# POWER.net
KiCad netlist of a schematic drawn in Altium Designer
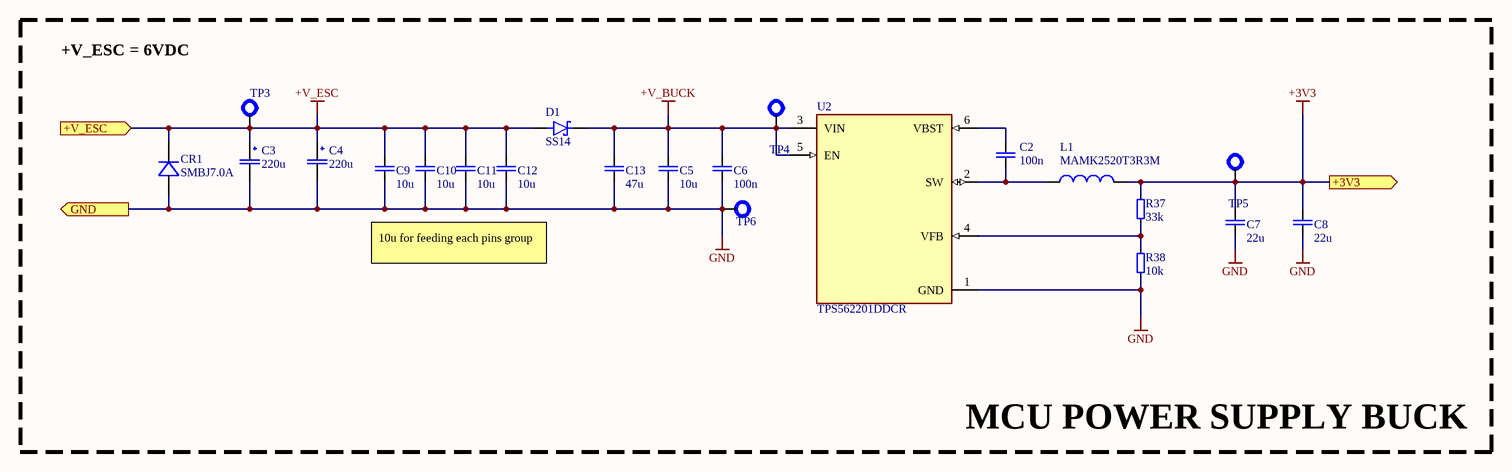
[diagram p0: POWER.SchDoc]

(export (version "E")
  (design (tool "Eeschema 10.0.6"))
  (components
    (comp (ref "C2")
      (value "100n")
      (footprint "C0402")
      (description "Generic SMD 0402 Ceramic Capacitor")
      (libsource (lib "PolSl Racing - Electrical") (part "Capacitor"))
    )
    (comp (ref "C3")
      (value "220u")
      (footprint "CAP_PC_8X10_NCH")
      (description "No Description Available")
      (fields
        (field (name "MANUFACTURER_PART_NUMBER") "PCJ1C221MCL4GS")
        (field (name "COPYRIGHT") "Copyright (C) 2026 Ultra Librarian. All rights reserved.")
      )
      (libsource (lib "Tractor2000") (part "PCJ1C221MCL4GS"))
    )
    (comp (ref "C4")
      (value "220u")
      (footprint "CAP_PC_8X10_NCH")
      (description "No Description Available")
      (fields
        (field (name "MANUFACTURER_PART_NUMBER") "PCJ1C221MCL4GS")
        (field (name "COPYRIGHT") "Copyright (C) 2026 Ultra Librarian. All rights reserved.")
      )
      (libsource (lib "Tractor2000") (part "PCJ1C221MCL4GS"))
    )
    (comp (ref "C5")
      (value "10u")
      (footprint "C0603")
      (description "Generic 0603 SMD Ceramic Capacitor")
      (libsource (lib "PolSl Racing - Electrical") (part "Capacitor"))
    )
    (comp (ref "C6")
      (value "100n")
      (footprint "C0603")
      (description "Generic 0603 SMD Ceramic Capacitor")
      (libsource (lib "PolSl Racing - Electrical") (part "Capacitor"))
    )
    (comp (ref "C7")
      (value "22u")
      (footprint "C0603")
      (description "Generic 0603 SMD Ceramic Capacitor")
      (libsource (lib "PolSl Racing - Electrical") (part "Capacitor"))
    )
    (comp (ref "C8")
      (value "22u")
      (footprint "C0603")
      (description "Generic 0603 SMD Ceramic Capacitor")
      (libsource (lib "PolSl Racing - Electrical") (part "Capacitor"))
    )
    (comp (ref "C9")
      (value "10u")
      (footprint "C0805")
      (description "Generic 0805 SMD Ceramic Capacitor")
      (libsource (lib "PolSl Racing - Electrical") (part "Capacitor"))
    )
    (comp (ref "C10")
      (value "10u")
      (footprint "C0805")
      (description "Generic 0805 SMD Ceramic Capacitor")
      (libsource (lib "PolSl Racing - Electrical") (part "Capacitor"))
    )
    (comp (ref "C11")
      (value "10u")
      (footprint "C0805")
      (description "Generic 0805 SMD Ceramic Capacitor")
      (libsource (lib "PolSl Racing - Electrical") (part "Capacitor"))
    )
    (comp (ref "C12")
      (value "10u")
      (footprint "C0805")
      (description "Generic 0805 SMD Ceramic Capacitor")
      (libsource (lib "PolSl Racing - Electrical") (part "Capacitor"))
    )
    (comp (ref "C13")
      (value "47u")
      (footprint "C1210")
      (description "Generic 1210 SMD Ceramic Capacitor")
      (libsource (lib "PolSl Racing - Electrical") (part "Capacitor"))
    )
    (comp (ref "CR1")
      (value "SMBJ7.0A")
      (footprint "SMBJSeries_LTF")
      (description "Description")
      (fields (field (name "COPYRIGHT") "Copyright (C) 2025 Ultra Librarian. All rights reserved."))
      (libsource (lib "Tractor2000") (part "SMBJ7.0A"))
    )
    (comp (ref "D1")
      (value "SS14")
      (footprint "DIOM4325X250N")
      (description "1A, 40V, Schottky Rectifier")
      (fields (field (name "MF") "Taiwan Semiconductor"))
      (libsource (lib "Tractor2000") (part "SS14"))
    )
    (comp (ref "L1")
      (value "MAMK2520T3R3M")
      (footprint "INDC2520X120N")
      (description "3.3 ÂµH Shielded Drum Core, Wirewound Inductor 1.7 A 156mOhm Max 1008 (2520 Metric)")
      (fields (field (name "MF") "Taiyo Yuden"))
      (libsource (lib "Tractor2000") (part "MAMK2520T3R3M"))
    )
    (comp (ref "R37")
      (value "33k")
      (footprint "R0402")
      (description "Generic 0402 SMD Resistor")
      (libsource (lib "PolSl Racing - Electrical") (part "Resistor"))
    )
    (comp (ref "R38")
      (value "10k")
      (footprint "R0402")
      (description "Generic 0402 SMD Resistor")
      (libsource (lib "PolSl Racing - Electrical") (part "Resistor"))
    )
    (comp (ref "TP3") (value "TP") (footprint "TP") (libsource (lib "Tractor2000") (part "TP")))
    (comp (ref "TP4") (value "TP") (footprint "TP") (libsource (lib "Tractor2000") (part "TP")))
    (comp (ref "TP5") (value "TP") (footprint "TP") (libsource (lib "Tractor2000") (part "TP")))
    (comp (ref "TP6") (value "TP") (footprint "TP") (libsource (lib "Tractor2000") (part "TP")))
    (comp (ref "U2")
      (value "TPS562201DDCR")
      (footprint "SOT95P280X110-6N")
      (description "4.5 V to 17 V input, 2 A output, synchronous step-down converter in Eco-mode")
      (fields (field (name "MF") "Texas Instruments"))
      (libsource (lib "Tractor2000") (part "TPS562201DDCR"))
    )
  )
  (nets
    (net (code "1") (name "+3V3") (class "Default")
      (node (ref "C7") (pin "2") (pinfunction "2_2") (pintype "passive"))
      (node (ref "C8") (pin "2") (pinfunction "2_2") (pintype "passive"))
      (node (ref "L1") (pin "2") (pinfunction "2_2") (pintype "passive"))
      (node (ref "R37") (pin "2") (pinfunction "2_2") (pintype "passive"))
    )
    (net (code "2") (name "+V_BUCK") (class "Default")
      (node (ref "C13") (pin "2") (pinfunction "2_2") (pintype "passive"))
      (node (ref "C5") (pin "2") (pinfunction "2_2") (pintype "passive"))
      (node (ref "C6") (pin "2") (pinfunction "2_2") (pintype "passive"))
      (node (ref "D1") (pin "C") (pinfunction "K_C") (pintype "passive"))
      (node (ref "U2") (pin "3") (pinfunction "VIN_3") (pintype "power_in"))
      (node (ref "U2") (pin "5") (pinfunction "EN_5") (pintype "input"))
    )
    (net (code "3") (name "+V_ESC") (class "Default")
      (node (ref "C10") (pin "2") (pinfunction "2_2") (pintype "passive"))
      (node (ref "C11") (pin "2") (pinfunction "2_2") (pintype "passive"))
      (node (ref "C12") (pin "2") (pinfunction "2_2") (pintype "passive"))
      (node (ref "C3") (pin "1") (pinfunction "1_1") (pintype "passive"))
      (node (ref "C4") (pin "1") (pinfunction "1_1") (pintype "passive"))
      (node (ref "C9") (pin "2") (pinfunction "2_2") (pintype "passive"))
      (node (ref "CR1") (pin "1") (pinfunction "1_1") (pintype "passive"))
      (node (ref "D1") (pin "A") (pinfunction "A_A") (pintype "passive"))
    )
    (net (code "4") (name "GND") (class "Default")
      (node (ref "C10") (pin "1") (pinfunction "1_1") (pintype "passive"))
      (node (ref "C11") (pin "1") (pinfunction "1_1") (pintype "passive"))
      (node (ref "C12") (pin "1") (pinfunction "1_1") (pintype "passive"))
      (node (ref "C13") (pin "1") (pinfunction "1_1") (pintype "passive"))
      (node (ref "C3") (pin "2") (pinfunction "2_2") (pintype "passive"))
      (node (ref "C4") (pin "2") (pinfunction "2_2") (pintype "passive"))
      (node (ref "C5") (pin "1") (pinfunction "1_1") (pintype "passive"))
      (node (ref "C6") (pin "1") (pinfunction "1_1") (pintype "passive"))
      (node (ref "C7") (pin "1") (pinfunction "1_1") (pintype "passive"))
      (node (ref "C8") (pin "1") (pinfunction "1_1") (pintype "passive"))
      (node (ref "C9") (pin "1") (pinfunction "1_1") (pintype "passive"))
      (node (ref "CR1") (pin "2") (pinfunction "2_2") (pintype "passive"))
      (node (ref "R38") (pin "1") (pinfunction "1_1") (pintype "passive"))
      (node (ref "U2") (pin "1") (pinfunction "GND_1") (pintype "power_in"))
    )
    (net (code "5") (name "Net-(U2-SW)") (class "Default")
      (node (ref "C2") (pin "1") (pinfunction "1_1") (pintype "passive"))
      (node (ref "L1") (pin "1") (pinfunction "1_1") (pintype "passive"))
      (node (ref "U2") (pin "2") (pinfunction "SW_2") (pintype "bidirectional"))
    )
    (net (code "6") (name "Net-(U2-VBST)") (class "Default")
      (node (ref "C2") (pin "2") (pinfunction "2_2") (pintype "passive"))
      (node (ref "U2") (pin "6") (pinfunction "VBST_6") (pintype "input"))
    )
    (net (code "7") (name "Net-(U2-VFB)") (class "Default")
      (node (ref "R37") (pin "1") (pinfunction "1_1") (pintype "passive"))
      (node (ref "R38") (pin "2") (pinfunction "2_2") (pintype "passive"))
      (node (ref "U2") (pin "4") (pinfunction "VFB_4") (pintype "input"))
    )
    (net (code "8") (name "unconnected-(TP3-Pad1)") (class "Default")
      (node (ref "TP3") (pin "1") (pinfunction "1_1") (pintype "passive"))
    )
    (net (code "9") (name "unconnected-(TP4-Pad1)") (class "Default")
      (node (ref "TP4") (pin "1") (pinfunction "1_1") (pintype "passive"))
    )
    (net (code "10") (name "unconnected-(TP5-Pad1)") (class "Default")
      (node (ref "TP5") (pin "1") (pinfunction "1_1") (pintype "passive"))
    )
    (net (code "11") (name "unconnected-(TP6-Pad1)") (class "Default")
      (node (ref "TP6") (pin "1") (pinfunction "1_1") (pintype "passive"))
    )
  )
)
